# bjt_trafo_ct.net
KiCad netlist of a schematic drawn in EAGLE
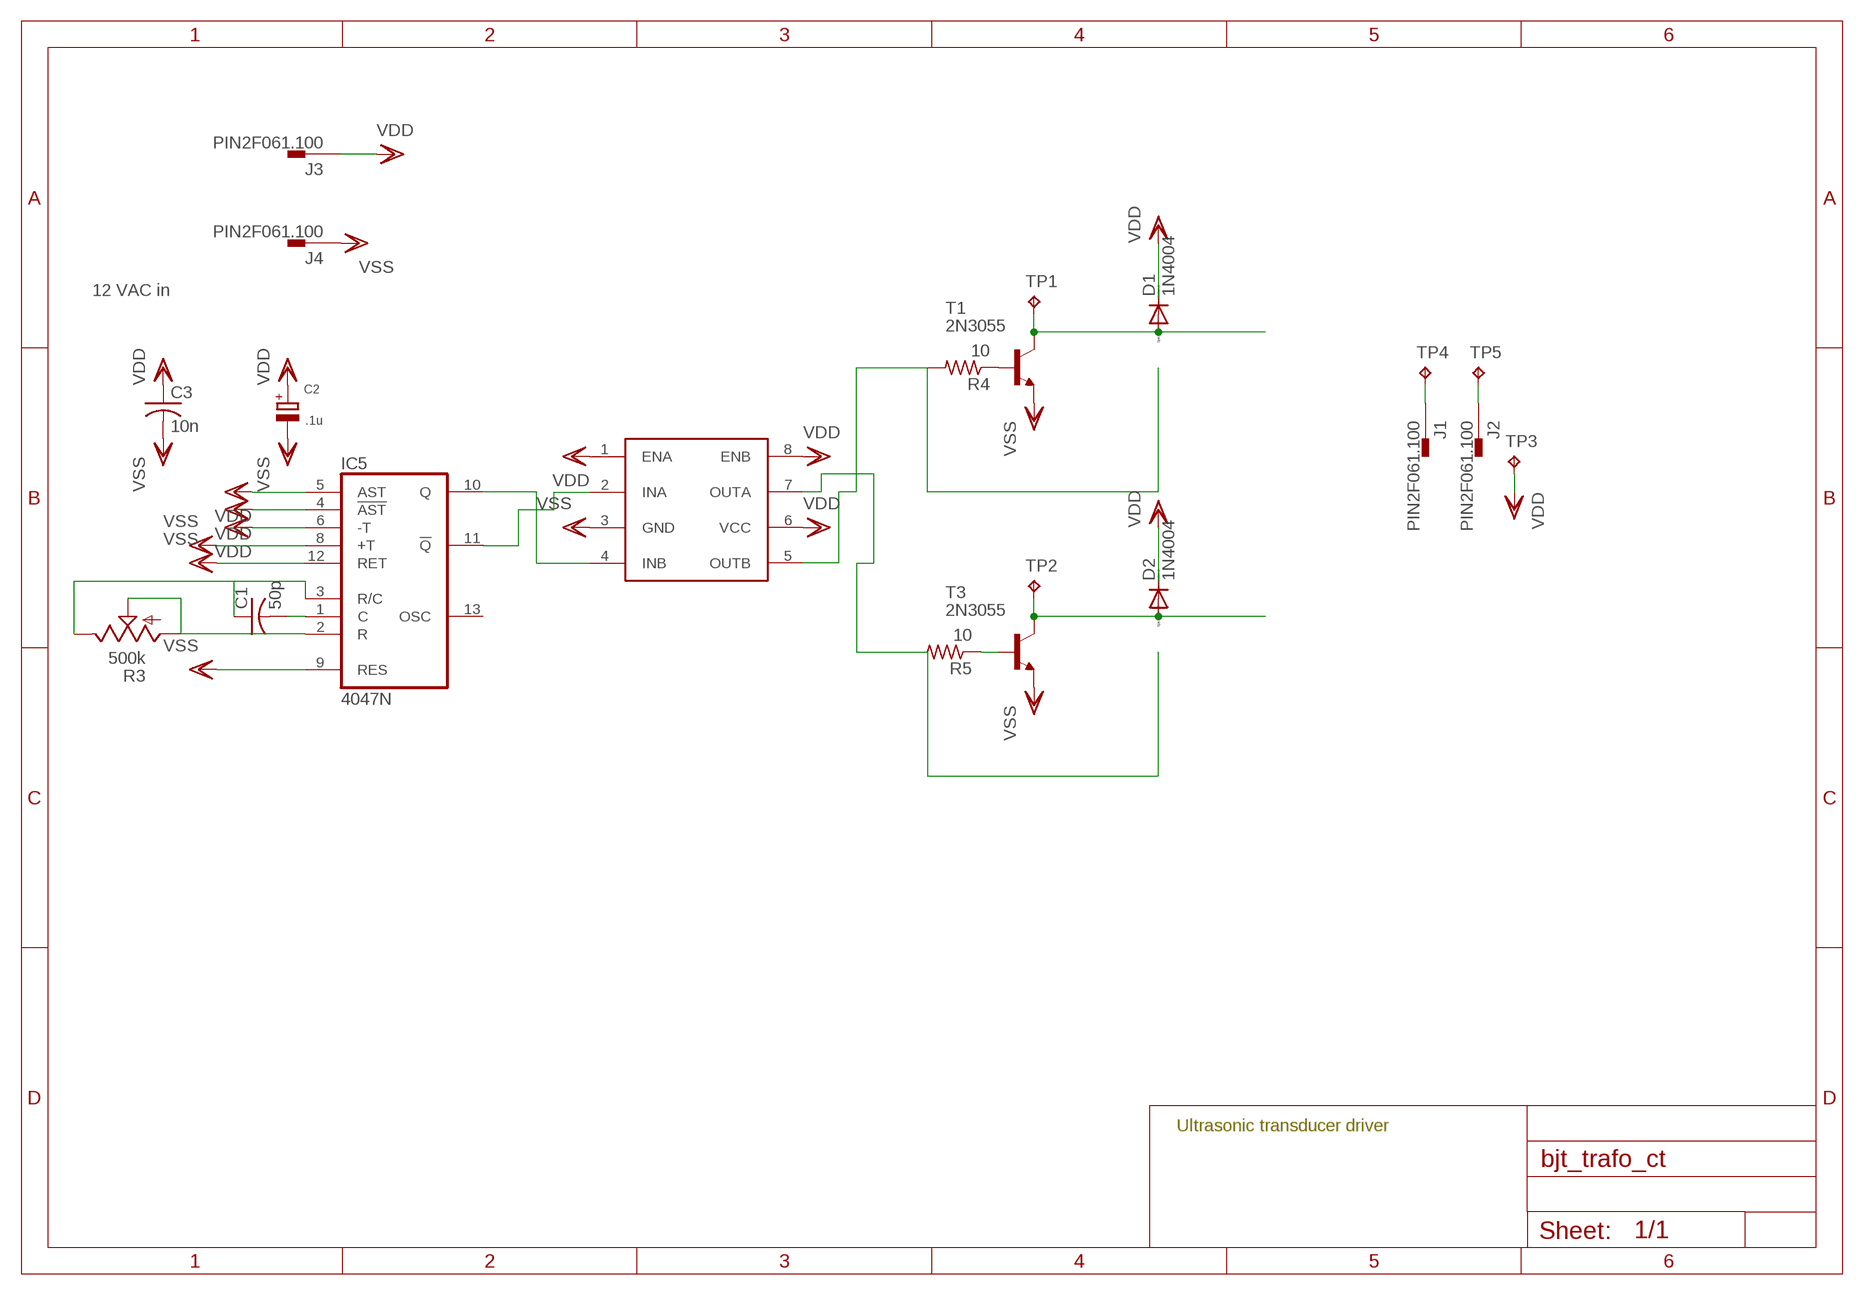
[diagram p0: schematic, sheet 1]

(export (version "E")
  (design (tool "Eeschema 10.0.6"))
  (components
    (comp (ref "C1")
      (value "50p")
      (footprint "eagle-import:C075-042X103")
      (libsource (lib "eagle-import") (part "C-US075-042X103"))
    )
    (comp (ref "C2")
      (value ".1u")
      (footprint "eagle-import:E5-8,5")
      (libsource (lib "eagle-import") (part "CPOL-EUE5-8.5"))
    )
    (comp (ref "C3")
      (value "10n")
      (footprint "eagle-import:C075-042X103")
      (libsource (lib "eagle-import") (part "C-US075-042X103"))
    )
    (comp (ref "D1")
      (value "1N4004")
      (footprint "eagle-import:DO41-10")
      (libsource (lib "eagle-import") (part "1N4004"))
    )
    (comp (ref "D2")
      (value "1N4004")
      (footprint "eagle-import:DO41-10")
      (libsource (lib "eagle-import") (part "1N4004"))
    )
    (comp (ref "IC5")
      (value "4047N")
      (footprint "eagle-import:DIL14")
      (libsource (lib "eagle-import") (part "4047N"))
    )
    (comp (ref "J1")
      (value "PIN2F061.100")
      (footprint "eagle-import:F061.100")
      (libsource (lib "eagle-import") (part "PIN2F061.100"))
    )
    (comp (ref "J2")
      (value "PIN2F061.100")
      (footprint "eagle-import:F061.100")
      (libsource (lib "eagle-import") (part "PIN2F061.100"))
    )
    (comp (ref "J3")
      (value "PIN2F061.100")
      (footprint "eagle-import:F061.100")
      (libsource (lib "eagle-import") (part "PIN2F061.100"))
    )
    (comp (ref "J4")
      (value "PIN2F061.100")
      (footprint "eagle-import:F061.100")
      (libsource (lib "eagle-import") (part "PIN2F061.100"))
    )
    (comp (ref "R3")
      (value "500k")
      (footprint "eagle-import:RJ9W")
      (libsource (lib "eagle-import") (part "TRIM_US-RJ9W"))
    )
    (comp (ref "R4")
      (value "10")
      (footprint "eagle-import:0207_10")
      (libsource (lib "eagle-import") (part "R-US_0207/10"))
    )
    (comp (ref "R5")
      (value "10")
      (footprint "eagle-import:0207_10")
      (libsource (lib "eagle-import") (part "R-US_0207/10"))
    )
    (comp (ref "T1")
      (value "2N3055")
      (footprint "eagle-import:TO3")
      (libsource (lib "eagle-import") (part "2N3055"))
    )
    (comp (ref "T3")
      (value "2N3055")
      (footprint "eagle-import:TO3")
      (libsource (lib "eagle-import") (part "2N3055"))
    )
    (comp (ref "TP1")
      (value "TPPAD1-20Y")
      (footprint "eagle-import:P1-20Y")
      (libsource (lib "eagle-import") (part "TPPAD1-20Y"))
    )
    (comp (ref "TP2")
      (value "TPPAD1-20Y")
      (footprint "eagle-import:P1-20Y")
      (libsource (lib "eagle-import") (part "TPPAD1-20Y"))
    )
    (comp (ref "TP3")
      (value "TPPAD1-20Y")
      (footprint "eagle-import:P1-20Y")
      (libsource (lib "eagle-import") (part "TPPAD1-20Y"))
    )
    (comp (ref "TP4")
      (value "TPPAD1-13Y")
      (footprint "eagle-import:P1-13Y")
      (libsource (lib "eagle-import") (part "TPPAD1-13Y"))
    )
    (comp (ref "TP5")
      (value "TPPAD1-13Y")
      (footprint "eagle-import:P1-13Y")
      (libsource (lib "eagle-import") (part "TPPAD1-13Y"))
    )
    (comp (ref "U$1")
      (value "UCC27425")
      (footprint "eagle-import:DIL08")
      (libsource (lib "eagle-import") (part "UCC27425"))
    )
  )
  (nets
    (net (code "1") (name "Net-(D1-PadA)") (class "Default")
      (node (ref "D1") (pin "A") (pinfunction "A_A") (pintype "passive"))
      (node (ref "T1") (pin "C") (pinfunction "C_C") (pintype "passive"))
      (node (ref "T1") (pin "C/") (pinfunction "C_C/") (pintype "passive"))
      (node (ref "TP1") (pin "TP") (pinfunction "TP_TP") (pintype "input"))
    )
    (net (code "2") (name "Net-(D2-PadA)") (class "Default")
      (node (ref "D2") (pin "A") (pinfunction "A_A") (pintype "passive"))
      (node (ref "T3") (pin "C") (pinfunction "C_C") (pintype "passive"))
      (node (ref "T3") (pin "C/") (pinfunction "C_C/") (pintype "passive"))
      (node (ref "TP2") (pin "TP") (pinfunction "TP_TP") (pintype "input"))
    )
    (net (code "3") (name "Net-(IC5A-C)") (class "Default")
      (node (ref "C1") (pin "2") (pinfunction "2_2") (pintype "passive"))
      (node (ref "IC5") (pin "1") (pinfunction "C_1") (pintype "input"))
    )
    (net (code "4") (name "Net-(IC5A-Q)") (class "Default")
      (node (ref "IC5") (pin "10") (pinfunction "Q_10") (pintype "output"))
      (node (ref "U$1") (pin "4") (pinfunction "INB_4") (pintype "bidirectional"))
    )
    (net (code "5") (name "Net-(IC5A-R)") (class "Default")
      (node (ref "IC5") (pin "2") (pinfunction "R_2") (pintype "input"))
      (node (ref "R3") (pin "A") (pinfunction "A_A") (pintype "passive"))
      (node (ref "R3") (pin "S") (pinfunction "S_S") (pintype "passive"))
    )
    (net (code "6") (name "Net-(IC5A-R{slash}C)") (class "Default")
      (node (ref "C1") (pin "1") (pinfunction "1_1") (pintype "passive"))
      (node (ref "IC5") (pin "3") (pinfunction "R/C_3") (pintype "input"))
      (node (ref "R3") (pin "E") (pinfunction "E_E") (pintype "passive"))
    )
    (net (code "7") (name "Net-(IC5A-~{Q})") (class "Default")
      (node (ref "IC5") (pin "11") (pinfunction "~{Q}_11") (pintype "output"))
      (node (ref "U$1") (pin "2") (pinfunction "INA_2") (pintype "bidirectional"))
    )
    (net (code "8") (name "Net-(J1-1-PadA1)") (class "Default")
      (node (ref "J1") (pin "A1") (pinfunction "1_A1") (pintype "passive"))
      (node (ref "J1") (pin "A2") (pinfunction "1_A2") (pintype "passive"))
      (node (ref "TP4") (pin "TP") (pinfunction "TP_TP") (pintype "input"))
    )
    (net (code "9") (name "Net-(J2-1-PadA1)") (class "Default")
      (node (ref "J2") (pin "A1") (pinfunction "1_A1") (pintype "passive"))
      (node (ref "J2") (pin "A2") (pinfunction "1_A2") (pintype "passive"))
      (node (ref "TP5") (pin "TP") (pinfunction "TP_TP") (pintype "input"))
    )
    (net (code "10") (name "Net-(R4-Pad1)") (class "Default")
      (node (ref "R4") (pin "1") (pinfunction "1_1") (pintype "passive"))
      (node (ref "T1") (pin "B") (pinfunction "B_B") (pintype "passive"))
    )
    (net (code "11") (name "Net-(R5-Pad1)") (class "Default")
      (node (ref "R5") (pin "1") (pinfunction "1_1") (pintype "passive"))
      (node (ref "T3") (pin "B") (pinfunction "B_B") (pintype "passive"))
    )
    (net (code "12") (name "Net-(U$1-OUTA)") (class "Default")
      (node (ref "R5") (pin "2") (pinfunction "2_2") (pintype "passive"))
      (node (ref "U$1") (pin "7") (pinfunction "OUTA_7") (pintype "bidirectional"))
    )
    (net (code "13") (name "Net-(U$1-OUTB)") (class "Default")
      (node (ref "R4") (pin "2") (pinfunction "2_2") (pintype "passive"))
      (node (ref "U$1") (pin "5") (pinfunction "OUTB_5") (pintype "bidirectional"))
    )
    (net (code "14") (name "VDD") (class "Default")
      (node (ref "C2") (pin "+") (pinfunction "+_+") (pintype "passive"))
      (node (ref "C3") (pin "1") (pinfunction "1_1") (pintype "passive"))
      (node (ref "D1") (pin "C") (pinfunction "C_C") (pintype "passive"))
      (node (ref "D2") (pin "C") (pinfunction "C_C") (pintype "passive"))
      (node (ref "IC5") (pin "4") (pinfunction "~{AST}_4") (pintype "input"))
      (node (ref "IC5") (pin "5") (pinfunction "AST_5") (pintype "input"))
      (node (ref "IC5") (pin "6") (pinfunction "-T_6") (pintype "input"))
      (node (ref "J3") (pin "A1") (pinfunction "1_A1") (pintype "passive"))
      (node (ref "J3") (pin "A2") (pinfunction "1_A2") (pintype "passive"))
      (node (ref "TP3") (pin "TP") (pinfunction "TP_TP") (pintype "input"))
      (node (ref "U$1") (pin "1") (pinfunction "ENA_1") (pintype "bidirectional"))
      (node (ref "U$1") (pin "6") (pinfunction "VCC_6") (pintype "bidirectional"))
      (node (ref "U$1") (pin "8") (pinfunction "ENB_8") (pintype "bidirectional"))
    )
    (net (code "15") (name "VSS") (class "Default")
      (node (ref "C2") (pin "-") (pinfunction "-_-") (pintype "passive"))
      (node (ref "C3") (pin "2") (pinfunction "2_2") (pintype "passive"))
      (node (ref "IC5") (pin "12") (pinfunction "RET_12") (pintype "input"))
      (node (ref "IC5") (pin "8") (pinfunction "+T_8") (pintype "input"))
      (node (ref "IC5") (pin "9") (pinfunction "RES_9") (pintype "input"))
      (node (ref "J4") (pin "A1") (pinfunction "1_A1") (pintype "passive"))
      (node (ref "J4") (pin "A2") (pinfunction "1_A2") (pintype "passive"))
      (node (ref "T1") (pin "E") (pinfunction "E_E") (pintype "passive"))
      (node (ref "T3") (pin "E") (pinfunction "E_E") (pintype "passive"))
      (node (ref "U$1") (pin "3") (pinfunction "GND_3") (pintype "bidirectional"))
    )
    (net (code "16") (name "unconnected-(IC5A-OSC-Pad13)") (class "Default")
      (node (ref "IC5") (pin "13") (pinfunction "OSC_13") (pintype "output"))
    )
  )
)
